# 3320.net
KiCad netlist of a schematic drawn in EAGLE
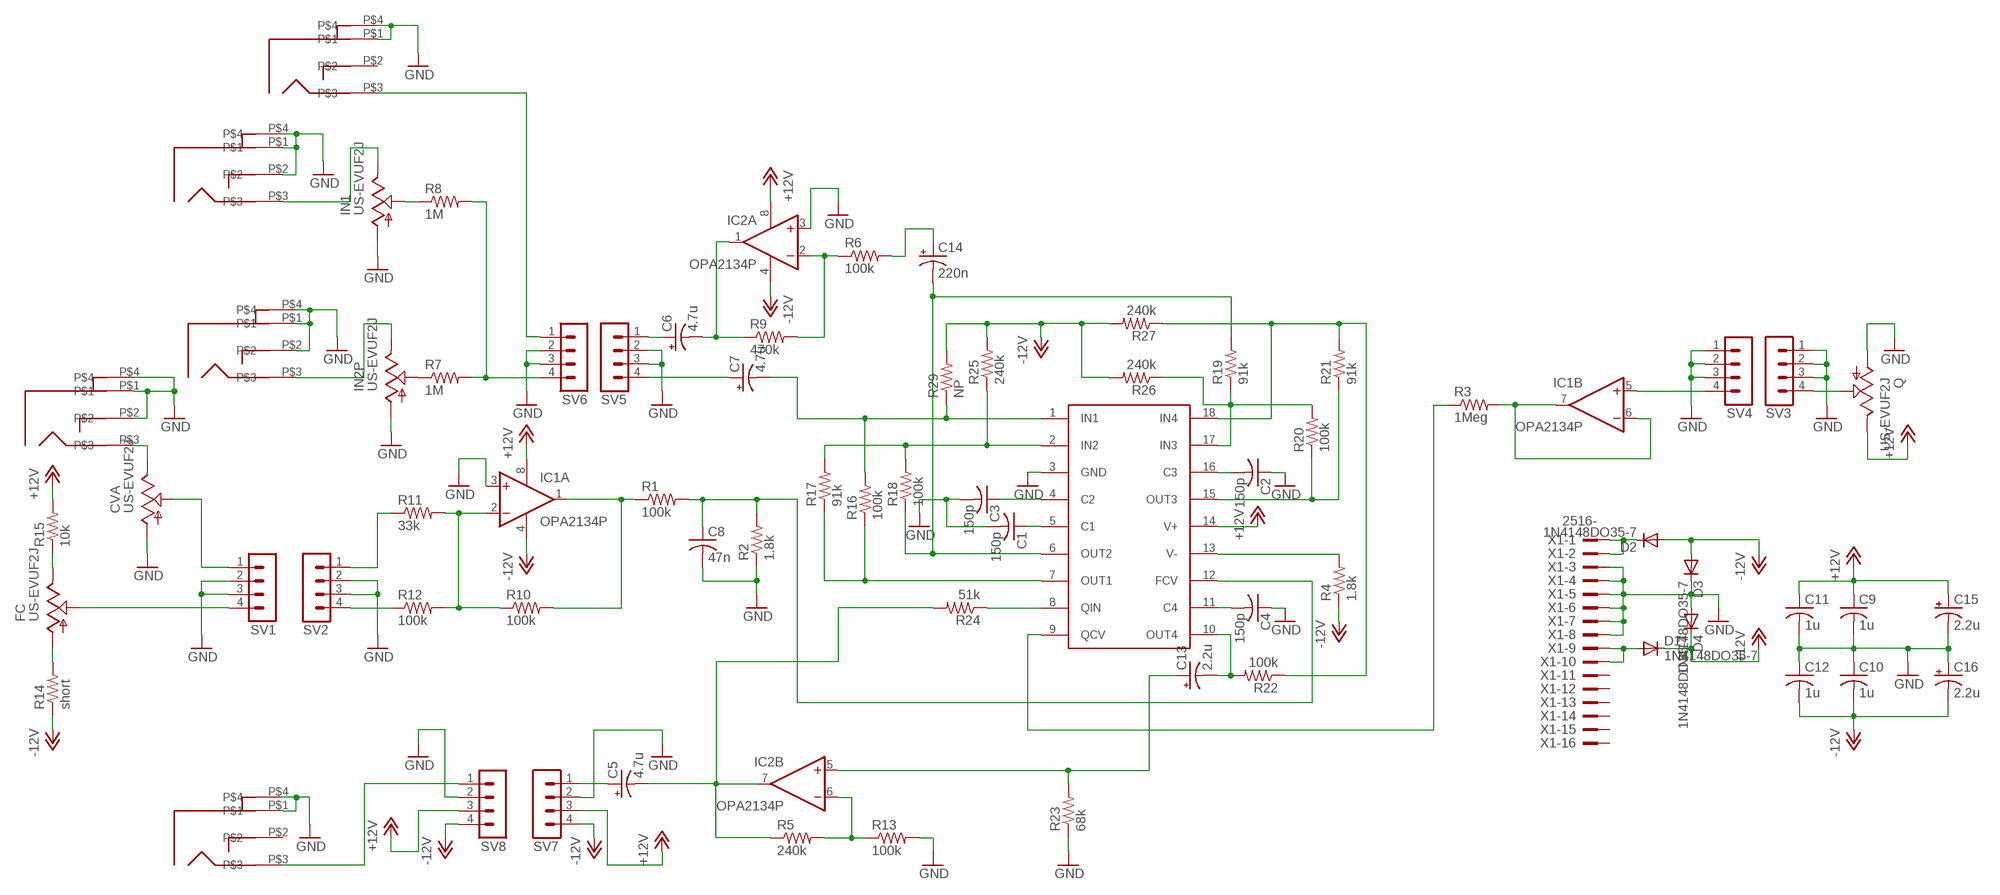
[diagram p0: schematic, sheet 1]

(export (version "E")
  (design (tool "Eeschema 10.0.6"))
  (components
    (comp (ref "2POUT")
      (value "PJ301BM")
      (footprint "eagle-import:PJ301BM")
      (libsource (lib "eagle-import") (part "PJ301BM"))
    )
    (comp (ref "4POUTPUT")
      (value "PJ301BM")
      (footprint "eagle-import:PJ301BM")
      (libsource (lib "eagle-import") (part "PJ301BM"))
    )
    (comp (ref "C1")
      (value "150p")
      (footprint "eagle-import:C050-025X075")
      (libsource (lib "eagle-import") (part "C-US050-025X075"))
    )
    (comp (ref "C2")
      (value "150p")
      (footprint "eagle-import:C050-025X075")
      (libsource (lib "eagle-import") (part "C-US050-025X075"))
    )
    (comp (ref "C3")
      (value "150p")
      (footprint "eagle-import:C050-025X075")
      (libsource (lib "eagle-import") (part "C-US050-025X075"))
    )
    (comp (ref "C4")
      (value "150p")
      (footprint "eagle-import:C050-025X075")
      (libsource (lib "eagle-import") (part "C-US050-025X075"))
    )
    (comp (ref "C5")
      (value "4.7u")
      (footprint "eagle-import:E2,5-6")
      (libsource (lib "eagle-import") (part "CPOL-USE2.5-6"))
    )
    (comp (ref "C6")
      (value "4.7u")
      (footprint "eagle-import:E2,5-6")
      (libsource (lib "eagle-import") (part "CPOL-USE2.5-6"))
    )
    (comp (ref "C7")
      (value "4.7u")
      (footprint "eagle-import:E2,5-6")
      (libsource (lib "eagle-import") (part "CPOL-USE2.5-6"))
    )
    (comp (ref "C8")
      (value "47n")
      (footprint "eagle-import:C050-025X075")
      (libsource (lib "eagle-import") (part "C-US050-025X075"))
    )
    (comp (ref "C9")
      (value "1u")
      (footprint "eagle-import:C050-025X075")
      (libsource (lib "eagle-import") (part "C-US050-025X075"))
    )
    (comp (ref "C10")
      (value "1u")
      (footprint "eagle-import:C050-025X075")
      (libsource (lib "eagle-import") (part "C-US050-025X075"))
    )
    (comp (ref "C11")
      (value "1u")
      (footprint "eagle-import:C050-025X075")
      (libsource (lib "eagle-import") (part "C-US050-025X075"))
    )
    (comp (ref "C12")
      (value "1u")
      (footprint "eagle-import:C050-025X075")
      (libsource (lib "eagle-import") (part "C-US050-025X075"))
    )
    (comp (ref "C13")
      (value "2.2u")
      (footprint "eagle-import:E2,5-6")
      (libsource (lib "eagle-import") (part "CPOL-USE2.5-6"))
    )
    (comp (ref "C14")
      (value "220n")
      (footprint "eagle-import:E2,5-6")
      (libsource (lib "eagle-import") (part "CPOL-USE2.5-6"))
    )
    (comp (ref "C15")
      (value "2.2u")
      (footprint "eagle-import:E2,5-6")
      (libsource (lib "eagle-import") (part "CPOL-USE2.5-6"))
    )
    (comp (ref "C16")
      (value "2.2u")
      (footprint "eagle-import:E2,5-6")
      (libsource (lib "eagle-import") (part "CPOL-USE2.5-6"))
    )
    (comp (ref "CVA")
      (value "US-EVUF2J")
      (footprint "eagle-import:EVUFXJ")
      (libsource (lib "eagle-import") (part "US-EVUF2J"))
    )
    (comp (ref "CVIN")
      (value "PJ301BM")
      (footprint "eagle-import:PJ301BM")
      (libsource (lib "eagle-import") (part "PJ301BM"))
    )
    (comp (ref "D1")
      (value "1N4148DO35-7")
      (footprint "eagle-import:DO35-7")
      (libsource (lib "eagle-import") (part "1N4148DO35-7"))
    )
    (comp (ref "D2")
      (value "1N4148DO35-7")
      (footprint "eagle-import:DO35-7")
      (libsource (lib "eagle-import") (part "1N4148DO35-7"))
    )
    (comp (ref "D3")
      (value "1N4148DO35-7")
      (footprint "eagle-import:DO35-7")
      (libsource (lib "eagle-import") (part "1N4148DO35-7"))
    )
    (comp (ref "D4")
      (value "1N4148DO35-7")
      (footprint "eagle-import:DO35-7")
      (libsource (lib "eagle-import") (part "1N4148DO35-7"))
    )
    (comp (ref "FC")
      (value "US-EVUF2J")
      (footprint "eagle-import:EVUFXJ")
      (libsource (lib "eagle-import") (part "US-EVUF2J"))
    )
    (comp (ref "IC1")
      (value "OPA2134P")
      (footprint "eagle-import:DIL08")
      (libsource (lib "eagle-import") (part "OPA2134P"))
    )
    (comp (ref "IC2")
      (value "OPA2134P")
      (footprint "eagle-import:DIL08")
      (libsource (lib "eagle-import") (part "OPA2134P"))
    )
    (comp (ref "IN")
      (value "PJ301BM")
      (footprint "eagle-import:PJ301BM")
      (libsource (lib "eagle-import") (part "PJ301BM"))
    )
    (comp (ref "IN1")
      (value "US-EVUF2J")
      (footprint "eagle-import:EVUFXJ")
      (libsource (lib "eagle-import") (part "US-EVUF2J"))
    )
    (comp (ref "IN2")
      (value "PJ301BM")
      (footprint "eagle-import:PJ301BM")
      (libsource (lib "eagle-import") (part "PJ301BM"))
    )
    (comp (ref "IN2P")
      (value "US-EVUF2J")
      (footprint "eagle-import:EVUFXJ")
      (libsource (lib "eagle-import") (part "US-EVUF2J"))
    )
    (comp (ref "Q")
      (value "US-EVUF2J")
      (footprint "eagle-import:EVUFXJ")
      (libsource (lib "eagle-import") (part "US-EVUF2J"))
    )
    (comp (ref "R1")
      (value "100k")
      (footprint "eagle-import:0207_2V")
      (libsource (lib "eagle-import") (part "R-US_0207/2V"))
    )
    (comp (ref "R2")
      (value "1.8k")
      (footprint "eagle-import:0207_2V")
      (libsource (lib "eagle-import") (part "R-US_0207/2V"))
    )
    (comp (ref "R3")
      (value "1Meg")
      (footprint "eagle-import:0207_2V")
      (libsource (lib "eagle-import") (part "R-US_0207/2V"))
    )
    (comp (ref "R4")
      (value "1.8k")
      (footprint "eagle-import:0207_2V")
      (libsource (lib "eagle-import") (part "R-US_0207/2V"))
    )
    (comp (ref "R5")
      (value "240k")
      (footprint "eagle-import:0207_2V")
      (libsource (lib "eagle-import") (part "R-US_0207/2V"))
    )
    (comp (ref "R6")
      (value "100k")
      (footprint "eagle-import:0207_2V")
      (libsource (lib "eagle-import") (part "R-US_0207/2V"))
    )
    (comp (ref "R7")
      (value "1M")
      (footprint "eagle-import:0204_7")
      (libsource (lib "eagle-import") (part "R-US_0204/7"))
    )
    (comp (ref "R8")
      (value "1M")
      (footprint "eagle-import:0204_7")
      (libsource (lib "eagle-import") (part "R-US_0204/7"))
    )
    (comp (ref "R9")
      (value "470k")
      (footprint "eagle-import:0207_2V")
      (libsource (lib "eagle-import") (part "R-US_0207/2V"))
    )
    (comp (ref "R10")
      (value "100k")
      (footprint "eagle-import:0207_2V")
      (libsource (lib "eagle-import") (part "R-US_0207/2V"))
    )
    (comp (ref "R11")
      (value "33k")
      (footprint "eagle-import:0207_2V")
      (libsource (lib "eagle-import") (part "R-US_0207/2V"))
    )
    (comp (ref "R12")
      (value "100k")
      (footprint "eagle-import:0207_2V")
      (libsource (lib "eagle-import") (part "R-US_0207/2V"))
    )
    (comp (ref "R13")
      (value "100k")
      (footprint "eagle-import:0207_2V")
      (libsource (lib "eagle-import") (part "R-US_0207/2V"))
    )
    (comp (ref "R14")
      (value "short")
      (footprint "eagle-import:0204_7")
      (libsource (lib "eagle-import") (part "R-US_0204/7"))
    )
    (comp (ref "R15")
      (value "10k")
      (footprint "eagle-import:0204_7")
      (libsource (lib "eagle-import") (part "R-US_0204/7"))
    )
    (comp (ref "R16")
      (value "100k")
      (footprint "eagle-import:0207_2V")
      (libsource (lib "eagle-import") (part "R-US_0207/2V"))
    )
    (comp (ref "R17")
      (value "91k")
      (footprint "eagle-import:0207_2V")
      (libsource (lib "eagle-import") (part "R-US_0207/2V"))
    )
    (comp (ref "R18")
      (value "100k")
      (footprint "eagle-import:0207_2V")
      (libsource (lib "eagle-import") (part "R-US_0207/2V"))
    )
    (comp (ref "R19")
      (value "91k")
      (footprint "eagle-import:0207_2V")
      (libsource (lib "eagle-import") (part "R-US_0207/2V"))
    )
    (comp (ref "R20")
      (value "100k")
      (footprint "eagle-import:0207_2V")
      (libsource (lib "eagle-import") (part "R-US_0207/2V"))
    )
    (comp (ref "R21")
      (value "91k")
      (footprint "eagle-import:0207_2V")
      (libsource (lib "eagle-import") (part "R-US_0207/2V"))
    )
    (comp (ref "R22")
      (value "100k")
      (footprint "eagle-import:0207_2V")
      (libsource (lib "eagle-import") (part "R-US_0207/2V"))
    )
    (comp (ref "R23")
      (value "68k")
      (footprint "eagle-import:0207_2V")
      (libsource (lib "eagle-import") (part "R-US_0207/2V"))
    )
    (comp (ref "R24")
      (value "51k")
      (footprint "eagle-import:0207_2V")
      (libsource (lib "eagle-import") (part "R-US_0207/2V"))
    )
    (comp (ref "R25")
      (value "240k")
      (footprint "eagle-import:0207_2V")
      (libsource (lib "eagle-import") (part "R-US_0207/2V"))
    )
    (comp (ref "R26")
      (value "240k")
      (footprint "eagle-import:0207_2V")
      (libsource (lib "eagle-import") (part "R-US_0207/2V"))
    )
    (comp (ref "R27")
      (value "240k")
      (footprint "eagle-import:0207_2V")
      (libsource (lib "eagle-import") (part "R-US_0207/2V"))
    )
    (comp (ref "R29")
      (value "NP")
      (footprint "eagle-import:0207_2V")
      (libsource (lib "eagle-import") (part "R-US_0207/2V"))
    )
    (comp (ref "SV1")
      (value "MA04-1")
      (footprint "eagle-import:MA04-1")
      (libsource (lib "eagle-import") (part "MA04-1"))
    )
    (comp (ref "SV2")
      (value "MA04-1")
      (footprint "eagle-import:MA04-1")
      (libsource (lib "eagle-import") (part "MA04-1"))
    )
    (comp (ref "SV3")
      (value "MA04-1")
      (footprint "eagle-import:MA04-1")
      (libsource (lib "eagle-import") (part "MA04-1"))
    )
    (comp (ref "SV4")
      (value "MA04-1")
      (footprint "eagle-import:MA04-1")
      (libsource (lib "eagle-import") (part "MA04-1"))
    )
    (comp (ref "SV5")
      (value "MA04-1")
      (footprint "eagle-import:MA04-1")
      (libsource (lib "eagle-import") (part "MA04-1"))
    )
    (comp (ref "SV6")
      (value "MA04-1")
      (footprint "eagle-import:MA04-1")
      (libsource (lib "eagle-import") (part "MA04-1"))
    )
    (comp (ref "SV7")
      (value "MA04-1")
      (footprint "eagle-import:MA04-1")
      (libsource (lib "eagle-import") (part "MA04-1"))
    )
    (comp (ref "SV8")
      (value "MA04-1")
      (footprint "eagle-import:MA04-1")
      (libsource (lib "eagle-import") (part "MA04-1"))
    )
    (comp (ref "U$1")
      (value "CEM3320")
      (footprint "eagle-import:DIL18")
      (libsource (lib "eagle-import") (part "CEM3320"))
    )
    (comp (ref "X1")
      (value "2516-")
      (footprint "eagle-import:PAK100_2500-16")
      (libsource (lib "eagle-import") (part "2516-"))
    )
  )
  (nets
    (net (code "1") (name "+12V") (class "Default")
      (node (ref "C11") (pin "1") (pinfunction "1_1") (pintype "passive"))
      (node (ref "C15") (pin "+") (pinfunction "+_+") (pintype "passive"))
      (node (ref "C9") (pin "1") (pinfunction "1_1") (pintype "passive"))
      (node (ref "D1") (pin "C") (pinfunction "C_C") (pintype "passive"))
      (node (ref "D4") (pin "C") (pinfunction "C_C") (pintype "passive"))
      (node (ref "IC1") (pin "8") (pinfunction "V+_8") (pintype "power_in"))
      (node (ref "IC2") (pin "8") (pinfunction "V+_8") (pintype "power_in"))
      (node (ref "Q") (pin "3") (pinfunction "E_3") (pintype "passive"))
      (node (ref "R15") (pin "2") (pinfunction "2_2") (pintype "passive"))
      (node (ref "SV7") (pin "3") (pinfunction "3_3") (pintype "passive"))
      (node (ref "SV8") (pin "3") (pinfunction "3_3") (pintype "passive"))
      (node (ref "U$1") (pin "14") (pinfunction "V+_14") (pintype "bidirectional"))
    )
    (net (code "2") (name "-12V") (class "Default")
      (node (ref "C10") (pin "2") (pinfunction "2_2") (pintype "passive"))
      (node (ref "C12") (pin "2") (pinfunction "2_2") (pintype "passive"))
      (node (ref "C16") (pin "-") (pinfunction "-_-") (pintype "passive"))
      (node (ref "D2") (pin "A") (pinfunction "A_A") (pintype "passive"))
      (node (ref "D3") (pin "A") (pinfunction "A_A") (pintype "passive"))
      (node (ref "IC1") (pin "4") (pinfunction "V-_4") (pintype "power_in"))
      (node (ref "IC2") (pin "4") (pinfunction "V-_4") (pintype "power_in"))
      (node (ref "R14") (pin "1") (pinfunction "1_1") (pintype "passive"))
      (node (ref "R25") (pin "2") (pinfunction "2_2") (pintype "passive"))
      (node (ref "R26") (pin "2") (pinfunction "2_2") (pintype "passive"))
      (node (ref "R27") (pin "2") (pinfunction "2_2") (pintype "passive"))
      (node (ref "R29") (pin "2") (pinfunction "2_2") (pintype "passive"))
      (node (ref "R4") (pin "1") (pinfunction "1_1") (pintype "passive"))
      (node (ref "SV7") (pin "4") (pinfunction "4_4") (pintype "passive"))
      (node (ref "SV8") (pin "4") (pinfunction "4_4") (pintype "passive"))
    )
    (net (code "3") (name "GND") (class "Default")
      (node (ref "2POUT") (pin "P$1") (pinfunction "P$1_P$1") (pintype "bidirectional"))
      (node (ref "2POUT") (pin "P$4") (pinfunction "P$4_P$4") (pintype "bidirectional"))
      (node (ref "4POUTPUT") (pin "P$1") (pinfunction "P$1_P$1") (pintype "bidirectional"))
      (node (ref "4POUTPUT") (pin "P$4") (pinfunction "P$4_P$4") (pintype "bidirectional"))
      (node (ref "C1") (pin "2") (pinfunction "2_2") (pintype "passive"))
      (node (ref "C10") (pin "1") (pinfunction "1_1") (pintype "passive"))
      (node (ref "C11") (pin "2") (pinfunction "2_2") (pintype "passive"))
      (node (ref "C12") (pin "1") (pinfunction "1_1") (pintype "passive"))
      (node (ref "C15") (pin "-") (pinfunction "-_-") (pintype "passive"))
      (node (ref "C16") (pin "+") (pinfunction "+_+") (pintype "passive"))
      (node (ref "C2") (pin "1") (pinfunction "1_1") (pintype "passive"))
      (node (ref "C3") (pin "2") (pinfunction "2_2") (pintype "passive"))
      (node (ref "C4") (pin "1") (pinfunction "1_1") (pintype "passive"))
      (node (ref "C8") (pin "2") (pinfunction "2_2") (pintype "passive"))
      (node (ref "C9") (pin "2") (pinfunction "2_2") (pintype "passive"))
      (node (ref "CVA") (pin "1") (pinfunction "A_1") (pintype "passive"))
      (node (ref "CVIN") (pin "P$1") (pinfunction "P$1_P$1") (pintype "bidirectional"))
      (node (ref "CVIN") (pin "P$2") (pinfunction "P$2_P$2") (pintype "bidirectional"))
      (node (ref "CVIN") (pin "P$4") (pinfunction "P$4_P$4") (pintype "bidirectional"))
      (node (ref "D3") (pin "C") (pinfunction "C_C") (pintype "passive"))
      (node (ref "D4") (pin "A") (pinfunction "A_A") (pintype "passive"))
      (node (ref "IC1") (pin "3") (pinfunction "+IN_3") (pintype "input"))
      (node (ref "IC2") (pin "3") (pinfunction "+IN_3") (pintype "input"))
      (node (ref "IN") (pin "P$1") (pinfunction "P$1_P$1") (pintype "bidirectional"))
      (node (ref "IN") (pin "P$2") (pinfunction "P$2_P$2") (pintype "bidirectional"))
      (node (ref "IN") (pin "P$4") (pinfunction "P$4_P$4") (pintype "bidirectional"))
      (node (ref "IN1") (pin "1") (pinfunction "A_1") (pintype "passive"))
      (node (ref "IN2") (pin "P$1") (pinfunction "P$1_P$1") (pintype "bidirectional"))
      (node (ref "IN2") (pin "P$2") (pinfunction "P$2_P$2") (pintype "bidirectional"))
      (node (ref "IN2") (pin "P$4") (pinfunction "P$4_P$4") (pintype "bidirectional"))
      (node (ref "IN2P") (pin "1") (pinfunction "A_1") (pintype "passive"))
      (node (ref "Q") (pin "1") (pinfunction "A_1") (pintype "passive"))
      (node (ref "R13") (pin "2") (pinfunction "2_2") (pintype "passive"))
      (node (ref "R2") (pin "1") (pinfunction "1_1") (pintype "passive"))
      (node (ref "R23") (pin "1") (pinfunction "1_1") (pintype "passive"))
      (node (ref "SV1") (pin "2") (pinfunction "2_2") (pintype "passive"))
      (node (ref "SV1") (pin "3") (pinfunction "3_3") (pintype "passive"))
      (node (ref "SV2") (pin "2") (pinfunction "2_2") (pintype "passive"))
      (node (ref "SV2") (pin "3") (pinfunction "3_3") (pintype "passive"))
      (node (ref "SV3") (pin "1") (pinfunction "1_1") (pintype "passive"))
      (node (ref "SV3") (pin "2") (pinfunction "2_2") (pintype "passive"))
      (node (ref "SV3") (pin "3") (pinfunction "3_3") (pintype "passive"))
      (node (ref "SV4") (pin "1") (pinfunction "1_1") (pintype "passive"))
      (node (ref "SV4") (pin "2") (pinfunction "2_2") (pintype "passive"))
      (node (ref "SV4") (pin "3") (pinfunction "3_3") (pintype "passive"))
      (node (ref "SV5") (pin "2") (pinfunction "2_2") (pintype "passive"))
      (node (ref "SV5") (pin "3") (pinfunction "3_3") (pintype "passive"))
      (node (ref "SV6") (pin "2") (pinfunction "2_2") (pintype "passive"))
      (node (ref "SV6") (pin "3") (pinfunction "3_3") (pintype "passive"))
      (node (ref "SV7") (pin "2") (pinfunction "2_2") (pintype "passive"))
      (node (ref "SV8") (pin "2") (pinfunction "2_2") (pintype "passive"))
      (node (ref "U$1") (pin "3") (pinfunction "GND_3") (pintype "bidirectional"))
      (node (ref "X1") (pin "3") (pinfunction "KL_3") (pintype "passive"))
      (node (ref "X1") (pin "4") (pinfunction "KL_4") (pintype "passive"))
      (node (ref "X1") (pin "5") (pinfunction "KL_5") (pintype "passive"))
      (node (ref "X1") (pin "6") (pinfunction "KL_6") (pintype "passive"))
      (node (ref "X1") (pin "7") (pinfunction "KL_7") (pintype "passive"))
      (node (ref "X1") (pin "8") (pinfunction "KL_8") (pintype "passive"))
    )
    (net (code "4") (name "Net-(2POUT-PadP$3)") (class "Default")
      (node (ref "2POUT") (pin "P$3") (pinfunction "P$3_P$3") (pintype "bidirectional"))
      (node (ref "SV6") (pin "1") (pinfunction "1_1") (pintype "passive"))
    )
    (net (code "5") (name "Net-(4POUTPUT-PadP$3)") (class "Default")
      (node (ref "4POUTPUT") (pin "P$3") (pinfunction "P$3_P$3") (pintype "bidirectional"))
      (node (ref "SV8") (pin "1") (pinfunction "1_1") (pintype "passive"))
    )
    (net (code "6") (name "Net-(C5-Pad+)") (class "Default")
      (node (ref "C5") (pin "+") (pinfunction "+_+") (pintype "passive"))
      (node (ref "SV7") (pin "1") (pinfunction "1_1") (pintype "passive"))
    )
    (net (code "7") (name "Net-(C6-Pad+)") (class "Default")
      (node (ref "C6") (pin "+") (pinfunction "+_+") (pintype "passive"))
      (node (ref "SV5") (pin "1") (pinfunction "1_1") (pintype "passive"))
    )
    (net (code "8") (name "Net-(C7-Pad+)") (class "Default")
      (node (ref "C7") (pin "+") (pinfunction "+_+") (pintype "passive"))
      (node (ref "SV5") (pin "4") (pinfunction "4_4") (pintype "passive"))
    )
    (net (code "9") (name "Net-(C14-Pad+)") (class "Default")
      (node (ref "C14") (pin "+") (pinfunction "+_+") (pintype "passive"))
      (node (ref "R6") (pin "2") (pinfunction "2_2") (pintype "passive"))
    )
    (net (code "10") (name "Net-(CVA-E)") (class "Default")
      (node (ref "CVA") (pin "3") (pinfunction "E_3") (pintype "passive"))
      (node (ref "CVIN") (pin "P$3") (pinfunction "P$3_P$3") (pintype "bidirectional"))
    )
    (net (code "11") (name "Net-(CVA-S)") (class "Default")
      (node (ref "CVA") (pin "2") (pinfunction "S_2") (pintype "passive"))
      (node (ref "SV1") (pin "1") (pinfunction "1_1") (pintype "passive"))
    )
    (net (code "12") (name "Net-(FC-A)") (class "Default")
      (node (ref "FC") (pin "1") (pinfunction "A_1") (pintype "passive"))
      (node (ref "R14") (pin "2") (pinfunction "2_2") (pintype "passive"))
    )
    (net (code "13") (name "Net-(FC-E)") (class "Default")
      (node (ref "FC") (pin "3") (pinfunction "E_3") (pintype "passive"))
      (node (ref "R15") (pin "1") (pinfunction "1_1") (pintype "passive"))
    )
    (net (code "14") (name "Net-(FC-S)") (class "Default")
      (node (ref "FC") (pin "2") (pinfunction "S_2") (pintype "passive"))
      (node (ref "SV1") (pin "4") (pinfunction "4_4") (pintype "passive"))
    )
    (net (code "15") (name "Net-(IC1A--IN)") (class "Default")
      (node (ref "IC1") (pin "2") (pinfunction "-IN_2") (pintype "input"))
      (node (ref "R10") (pin "1") (pinfunction "1_1") (pintype "passive"))
      (node (ref "R11") (pin "2") (pinfunction "2_2") (pintype "passive"))
      (node (ref "R12") (pin "2") (pinfunction "2_2") (pintype "passive"))
    )
    (net (code "16") (name "Net-(IC1A-OUT)") (class "Default")
      (node (ref "IC1") (pin "1") (pinfunction "OUT_1") (pintype "output"))
      (node (ref "R1") (pin "1") (pinfunction "1_1") (pintype "passive"))
      (node (ref "R10") (pin "2") (pinfunction "2_2") (pintype "passive"))
    )
    (net (code "17") (name "Net-(IC1B-+IN)") (class "Default")
      (node (ref "IC1") (pin "5") (pinfunction "+IN_5") (pintype "input"))
      (node (ref "SV4") (pin "4") (pinfunction "4_4") (pintype "passive"))
    )
    (net (code "18") (name "Net-(IC1B--IN)") (class "Default")
      (node (ref "IC1") (pin "6") (pinfunction "-IN_6") (pintype "input"))
      (node (ref "IC1") (pin "7") (pinfunction "OUT_7") (pintype "output"))
      (node (ref "R3") (pin "2") (pinfunction "2_2") (pintype "passive"))
    )
    (net (code "19") (name "Net-(IC2A--IN)") (class "Default")
      (node (ref "IC2") (pin "2") (pinfunction "-IN_2") (pintype "input"))
      (node (ref "R6") (pin "1") (pinfunction "1_1") (pintype "passive"))
      (node (ref "R9") (pin "2") (pinfunction "2_2") (pintype "passive"))
    )
    (net (code "20") (name "Net-(IC2A-OUT)") (class "Default")
      (node (ref "C6") (pin "-") (pinfunction "-_-") (pintype "passive"))
      (node (ref "IC2") (pin "1") (pinfunction "OUT_1") (pintype "output"))
      (node (ref "R9") (pin "1") (pinfunction "1_1") (pintype "passive"))
    )
    (net (code "21") (name "Net-(IC2B-+IN)") (class "Default")
      (node (ref "C13") (pin "+") (pinfunction "+_+") (pintype "passive"))
      (node (ref "IC2") (pin "5") (pinfunction "+IN_5") (pintype "input"))
      (node (ref "R23") (pin "2") (pinfunction "2_2") (pintype "passive"))
    )
    (net (code "22") (name "Net-(IC2B--IN)") (class "Default")
      (node (ref "IC2") (pin "6") (pinfunction "-IN_6") (pintype "input"))
      (node (ref "R13") (pin "1") (pinfunction "1_1") (pintype "passive"))
      (node (ref "R5") (pin "2") (pinfunction "2_2") (pintype "passive"))
    )
    (net (code "23") (name "Net-(IC2B-OUT)") (class "Default")
      (node (ref "C5") (pin "-") (pinfunction "-_-") (pintype "passive"))
      (node (ref "IC2") (pin "7") (pinfunction "OUT_7") (pintype "output"))
      (node (ref "R24") (pin "2") (pinfunction "2_2") (pintype "passive"))
      (node (ref "R5") (pin "1") (pinfunction "1_1") (pintype "passive"))
    )
    (net (code "24") (name "Net-(IN1-E)") (class "Default")
      (node (ref "IN") (pin "P$3") (pinfunction "P$3_P$3") (pintype "bidirectional"))
      (node (ref "IN1") (pin "3") (pinfunction "E_3") (pintype "passive"))
    )
    (net (code "25") (name "Net-(IN1-S)") (class "Default")
      (node (ref "IN1") (pin "2") (pinfunction "S_2") (pintype "passive"))
      (node (ref "R8") (pin "1") (pinfunction "1_1") (pintype "passive"))
    )
    (net (code "26") (name "Net-(IN2P-E)") (class "Default")
      (node (ref "IN2") (pin "P$3") (pinfunction "P$3_P$3") (pintype "bidirectional"))
      (node (ref "IN2P") (pin "3") (pinfunction "E_3") (pintype "passive"))
    )
    (net (code "27") (name "Net-(IN2P-S)") (class "Default")
      (node (ref "IN2P") (pin "2") (pinfunction "S_2") (pintype "passive"))
      (node (ref "R7") (pin "1") (pinfunction "1_1") (pintype "passive"))
    )
    (net (code "28") (name "Net-(Q-S)") (class "Default")
      (node (ref "Q") (pin "2") (pinfunction "S_2") (pintype "passive"))
      (node (ref "SV3") (pin "4") (pinfunction "4_4") (pintype "passive"))
    )
    (net (code "29") (name "Net-(R7-Pad2)") (class "Default")
      (node (ref "R7") (pin "2") (pinfunction "2_2") (pintype "passive"))
      (node (ref "R8") (pin "2") (pinfunction "2_2") (pintype "passive"))
      (node (ref "SV6") (pin "4") (pinfunction "4_4") (pintype "passive"))
    )
    (net (code "30") (name "Net-(R11-Pad1)") (class "Default")
      (node (ref "R11") (pin "1") (pinfunction "1_1") (pintype "passive"))
      (node (ref "SV2") (pin "1") (pinfunction "1_1") (pintype "passive"))
    )
    (net (code "31") (name "Net-(R12-Pad1)") (class "Default")
      (node (ref "R12") (pin "1") (pinfunction "1_1") (pintype "passive"))
      (node (ref "SV2") (pin "4") (pinfunction "4_4") (pintype "passive"))
    )
    (net (code "32") (name "Net-(U$1-C1)") (class "Default")
      (node (ref "C1") (pin "1") (pinfunction "1_1") (pintype "passive"))
      (node (ref "U$1") (pin "5") (pinfunction "C1_5") (pintype "bidirectional"))
    )
    (net (code "33") (name "Net-(U$1-C2)") (class "Default")
      (node (ref "C3") (pin "1") (pinfunction "1_1") (pintype "passive"))
      (node (ref "U$1") (pin "4") (pinfunction "C2_4") (pintype "bidirectional"))
    )
    (net (code "34") (name "Net-(U$1-C3)") (class "Default")
      (node (ref "C2") (pin "2") (pinfunction "2_2") (pintype "passive"))
      (node (ref "U$1") (pin "16") (pinfunction "C3_16") (pintype "bidirectional"))
    )
    (net (code "35") (name "Net-(U$1-C4)") (class "Default")
      (node (ref "C4") (pin "2") (pinfunction "2_2") (pintype "passive"))
      (node (ref "U$1") (pin "11") (pinfunction "C4_11") (pintype "bidirectional"))
    )
    (net (code "36") (name "Net-(U$1-FCV)") (class "Default")
      (node (ref "C8") (pin "1") (pinfunction "1_1") (pintype "passive"))
      (node (ref "R1") (pin "2") (pinfunction "2_2") (pintype "passive"))
      (node (ref "R2") (pin "2") (pinfunction "2_2") (pintype "passive"))
      (node (ref "U$1") (pin "12") (pinfunction "FCV_12") (pintype "bidirectional"))
    )
    (net (code "37") (name "Net-(U$1-IN1)") (class "Default")
      (node (ref "C7") (pin "-") (pinfunction "-_-") (pintype "passive"))
      (node (ref "R16") (pin "2") (pinfunction "2_2") (pintype "passive"))
      (node (ref "R29") (pin "1") (pinfunction "1_1") (pintype "passive"))
      (node (ref "U$1") (pin "1") (pinfunction "IN1_1") (pintype "bidirectional"))
    )
    (net (code "38") (name "Net-(U$1-IN2)") (class "Default")
      (node (ref "R17") (pin "2") (pinfunction "2_2") (pintype "passive"))
      (node (ref "R18") (pin "2") (pinfunction "2_2") (pintype "passive"))
      (node (ref "R25") (pin "1") (pinfunction "1_1") (pintype "passive"))
      (node (ref "U$1") (pin "2") (pinfunction "IN2_2") (pintype "bidirectional"))
    )
    (net (code "39") (name "Net-(U$1-IN3)") (class "Default")
      (node (ref "R19") (pin "1") (pinfunction "1_1") (pintype "passive"))
      (node (ref "R20") (pin "2") (pinfunction "2_2") (pintype "passive"))
      (node (ref "R26") (pin "1") (pinfunction "1_1") (pintype "passive"))
      (node (ref "U$1") (pin "17") (pinfunction "IN3_17") (pintype "bidirectional"))
    )
    (net (code "40") (name "Net-(U$1-IN4)") (class "Default")
      (node (ref "R21") (pin "2") (pinfunction "2_2") (pintype "passive"))
      (node (ref "R22") (pin "1") (pinfunction "1_1") (pintype "passive"))
      (node (ref "R27") (pin "1") (pinfunction "1_1") (pintype "passive"))
      (node (ref "U$1") (pin "18") (pinfunction "IN4_18") (pintype "bidirectional"))
    )
    (net (code "41") (name "Net-(U$1-OUT1)") (class "Default")
      (node (ref "R16") (pin "1") (pinfunction "1_1") (pintype "passive"))
      (node (ref "R17") (pin "1") (pinfunction "1_1") (pintype "passive"))
      (node (ref "U$1") (pin "7") (pinfunction "OUT1_7") (pintype "bidirectional"))
    )
    (net (code "42") (name "Net-(U$1-OUT2)") (class "Default")
      (node (ref "C14") (pin "-") (pinfunction "-_-") (pintype "passive"))
      (node (ref "R18") (pin "1") (pinfunction "1_1") (pintype "passive"))
      (node (ref "R19") (pin "2") (pinfunction "2_2") (pintype "passive"))
      (node (ref "U$1") (pin "6") (pinfunction "OUT2_6") (pintype "bidirectional"))
    )
    (net (code "43") (name "Net-(U$1-OUT3)") (class "Default")
      (node (ref "R20") (pin "1") (pinfunction "1_1") (pintype "passive"))
      (node (ref "R21") (pin "1") (pinfunction "1_1") (pintype "passive"))
      (node (ref "U$1") (pin "15") (pinfunction "OUT3_15") (pintype "bidirectional"))
    )
    (net (code "44") (name "Net-(U$1-OUT4)") (class "Default")
      (node (ref "C13") (pin "-") (pinfunction "-_-") (pintype "passive"))
      (node (ref "R22") (pin "2") (pinfunction "2_2") (pintype "passive"))
      (node (ref "U$1") (pin "10") (pinfunction "OUT4_10") (pintype "bidirectional"))
    )
    (net (code "45") (name "Net-(U$1-QCV)") (class "Default")
      (node (ref "R3") (pin "1") (pinfunction "1_1") (pintype "passive"))
      (node (ref "U$1") (pin "9") (pinfunction "QCV_9") (pintype "bidirectional"))
    )
    (net (code "46") (name "Net-(U$1-QIN)") (class "Default")
      (node (ref "R24") (pin "1") (pinfunction "1_1") (pintype "passive"))
      (node (ref "U$1") (pin "8") (pinfunction "QIN_8") (pintype "bidirectional"))
    )
    (net (code "47") (name "Net-(U$1-V-)") (class "Default")
      (node (ref "R4") (pin "2") (pinfunction "2_2") (pintype "passive"))
      (node (ref "U$1") (pin "13") (pinfunction "V-_13") (pintype "bidirectional"))
    )
    (net (code "48") (name "Net-(X1A-KL)") (class "Default")
      (node (ref "D2") (pin "C") (pinfunction "C_C") (pintype "passive"))
      (node (ref "X1") (pin "1") (pinfunction "KL_1") (pintype "passive"))
      (node (ref "X1") (pin "2") (pinfunction "KL_2") (pintype "passive"))
    )
    (net (code "49") (name "Net-(X1B-KL)") (class "Default")
      (node (ref "D1") (pin "A") (pinfunction "A_A") (pintype "passive"))
      (node (ref "X1") (pin "10") (pinfunction "KL_10") (pintype "passive"))
      (node (ref "X1") (pin "9") (pinfunction "KL_9") (pintype "passive"))
    )
    (net (code "50") (name "unconnected-(2POUT-PadP$2)") (class "Default")
      (node (ref "2POUT") (pin "P$2") (pinfunction "P$2_P$2") (pintype "bidirectional"))
    )
    (net (code "51") (name "unconnected-(4POUTPUT-PadP$2)") (class "Default")
      (node (ref "4POUTPUT") (pin "P$2") (pinfunction "P$2_P$2") (pintype "bidirectional"))
    )
    (net (code "52") (name "unconnected-(X1C-KL-Pad11)") (class "Default")
      (node (ref "X1") (pin "11") (pinfunction "KL_11") (pintype "passive"))
    )
    (net (code "53") (name "unconnected-(X1D-KL-Pad12)") (class "Default")
      (node (ref "X1") (pin "12") (pinfunction "KL_12") (pintype "passive"))
    )
    (net (code "54") (name "unconnected-(X1E-KL-Pad13)") (class "Default")
      (node (ref "X1") (pin "13") (pinfunction "KL_13") (pintype "passive"))
    )
    (net (code "55") (name "unconnected-(X1F-KL-Pad14)") (class "Default")
      (node (ref "X1") (pin "14") (pinfunction "KL_14") (pintype "passive"))
    )
    (net (code "56") (name "unconnected-(X1G-KL-Pad15)") (class "Default")
      (node (ref "X1") (pin "15") (pinfunction "KL_15") (pintype "passive"))
    )
    (net (code "57") (name "unconnected-(X1H-KL-Pad16)") (class "Default")
      (node (ref "X1") (pin "16") (pinfunction "KL_16") (pintype "passive"))
    )
  )
)
